# FPGA_Symbol1.net
KiCad netlist of a schematic drawn in Altium Designer
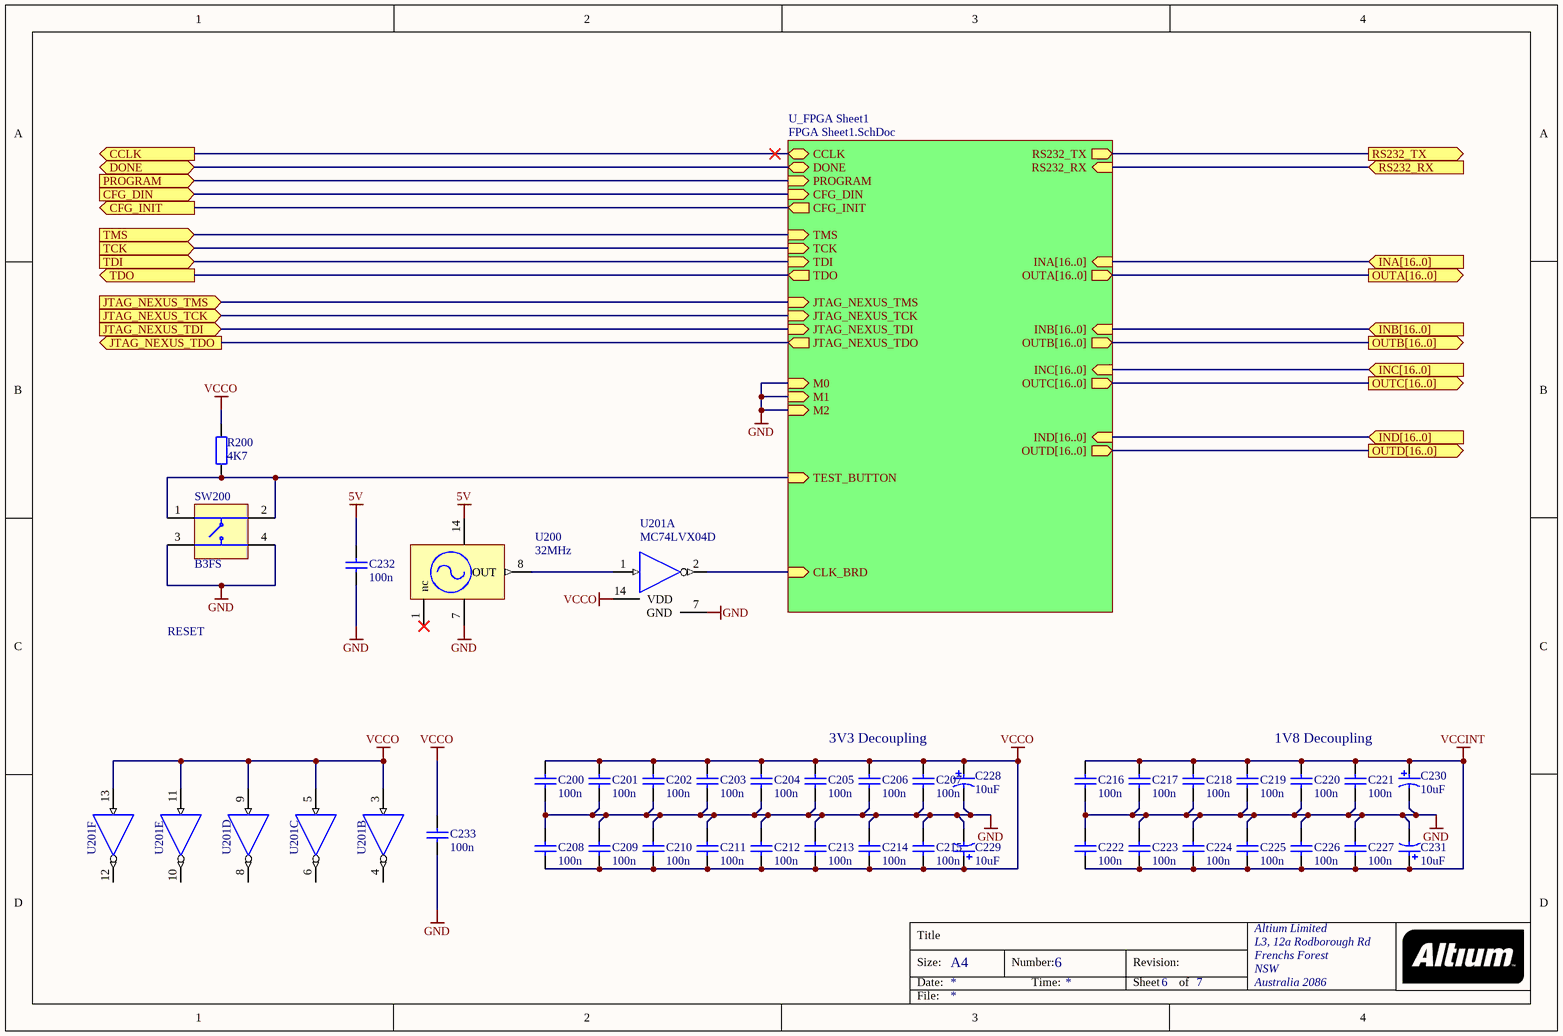
[diagram p0: FPGA Symbol1.SchDoc]

(export (version "E")
  (design (tool "Eeschema 10.0.6"))
  (components
    (comp (ref "C200")
      (value "100n")
      (footprint "BOC1_3:CC2012-0805")
      (description "Capacitor")
      (libsource (lib "BOC1_3") (part "CAP"))
    )
    (comp (ref "C201")
      (value "100n")
      (footprint "BOC1_3:CC2012-0805")
      (description "Capacitor")
      (libsource (lib "BOC1_3") (part "CAP"))
    )
    (comp (ref "C202")
      (value "100n")
      (footprint "BOC1_3:CC2012-0805")
      (description "Capacitor")
      (libsource (lib "BOC1_3") (part "CAP"))
    )
    (comp (ref "C203")
      (value "100n")
      (footprint "BOC1_3:CC2012-0805")
      (description "Capacitor")
      (libsource (lib "BOC1_3") (part "CAP"))
    )
    (comp (ref "C204")
      (value "100n")
      (footprint "BOC1_3:CC2012-0805")
      (description "Capacitor")
      (libsource (lib "BOC1_3") (part "CAP"))
    )
    (comp (ref "C205")
      (value "100n")
      (footprint "BOC1_3:CC2012-0805")
      (description "Capacitor")
      (libsource (lib "BOC1_3") (part "CAP"))
    )
    (comp (ref "C206")
      (value "100n")
      (footprint "BOC1_3:CC2012-0805")
      (description "Capacitor")
      (libsource (lib "BOC1_3") (part "CAP"))
    )
    (comp (ref "C207")
      (value "100n")
      (footprint "BOC1_3:CC2012-0805")
      (description "Capacitor")
      (libsource (lib "BOC1_3") (part "CAP"))
    )
    (comp (ref "C208")
      (value "100n")
      (footprint "BOC1_3:CC2012-0805")
      (description "Capacitor")
      (libsource (lib "BOC1_3") (part "CAP"))
    )
    (comp (ref "C209")
      (value "100n")
      (footprint "BOC1_3:CC2012-0805")
      (description "Capacitor")
      (libsource (lib "BOC1_3") (part "CAP"))
    )
    (comp (ref "C210")
      (value "100n")
      (footprint "BOC1_3:CC2012-0805")
      (description "Capacitor")
      (libsource (lib "BOC1_3") (part "CAP"))
    )
    (comp (ref "C211")
      (value "100n")
      (footprint "BOC1_3:CC2012-0805")
      (description "Capacitor")
      (libsource (lib "BOC1_3") (part "CAP"))
    )
    (comp (ref "C212")
      (value "100n")
      (footprint "BOC1_3:CC2012-0805")
      (description "Capacitor")
      (libsource (lib "BOC1_3") (part "CAP"))
    )
    (comp (ref "C213")
      (value "100n")
      (footprint "BOC1_3:CC2012-0805")
      (description "Capacitor")
      (libsource (lib "BOC1_3") (part "CAP"))
    )
    (comp (ref "C214")
      (value "100n")
      (footprint "BOC1_3:CC2012-0805")
      (description "Capacitor")
      (libsource (lib "BOC1_3") (part "CAP"))
    )
    (comp (ref "C215")
      (value "100n")
      (footprint "BOC1_3:CC2012-0805")
      (description "Capacitor")
      (libsource (lib "BOC1_3") (part "CAP"))
    )
    (comp (ref "C216")
      (value "100n")
      (footprint "BOC1_3:CC2012-0805")
      (description "Capacitor")
      (libsource (lib "BOC1_3") (part "CAP"))
    )
    (comp (ref "C217")
      (value "100n")
      (footprint "BOC1_3:CC2012-0805")
      (description "Capacitor")
      (libsource (lib "BOC1_3") (part "CAP"))
    )
    (comp (ref "C218")
      (value "100n")
      (footprint "BOC1_3:CC2012-0805")
      (description "Capacitor")
      (libsource (lib "BOC1_3") (part "CAP"))
    )
    (comp (ref "C219")
      (value "100n")
      (footprint "BOC1_3:CC2012-0805")
      (description "Capacitor")
      (libsource (lib "BOC1_3") (part "CAP"))
    )
    (comp (ref "C220")
      (value "100n")
      (footprint "BOC1_3:CC2012-0805")
      (description "Capacitor")
      (libsource (lib "BOC1_3") (part "CAP"))
    )
    (comp (ref "C221")
      (value "100n")
      (footprint "BOC1_3:CC2012-0805")
      (description "Capacitor")
      (libsource (lib "BOC1_3") (part "CAP"))
    )
    (comp (ref "C222")
      (value "100n")
      (footprint "BOC1_3:CC2012-0805")
      (description "Capacitor")
      (libsource (lib "BOC1_3") (part "CAP"))
    )
    (comp (ref "C223")
      (value "100n")
      (footprint "BOC1_3:CC2012-0805")
      (description "Capacitor")
      (libsource (lib "BOC1_3") (part "CAP"))
    )
    (comp (ref "C224")
      (value "100n")
      (footprint "BOC1_3:CC2012-0805")
      (description "Capacitor")
      (libsource (lib "BOC1_3") (part "CAP"))
    )
    (comp (ref "C225")
      (value "100n")
      (footprint "BOC1_3:CC2012-0805")
      (description "Capacitor")
      (libsource (lib "BOC1_3") (part "CAP"))
    )
    (comp (ref "C226")
      (value "100n")
      (footprint "BOC1_3:CC2012-0805")
      (description "Capacitor")
      (libsource (lib "BOC1_3") (part "CAP"))
    )
    (comp (ref "C227")
      (value "100n")
      (footprint "BOC1_3:CC2012-0805")
      (description "Capacitor")
      (libsource (lib "BOC1_3") (part "CAP"))
    )
    (comp (ref "C228")
      (value "10uF")
      (footprint "BOC1_3:MCCT-B")
      (description "Polar Capacitor")
      (libsource (lib "BOC1_3") (part "CAP_POLAR"))
    )
    (comp (ref "C229")
      (value "10uF")
      (footprint "BOC1_3:MCCT-B")
      (description "Polar Capacitor")
      (libsource (lib "BOC1_3") (part "CAP_POLAR"))
    )
    (comp (ref "C230")
      (value "10uF")
      (footprint "BOC1_3:MCCT-B")
      (description "Polar Capacitor")
      (libsource (lib "BOC1_3") (part "CAP_POLAR"))
    )
    (comp (ref "C231")
      (value "10uF")
      (footprint "BOC1_3:MCCT-B")
      (description "Polar Capacitor")
      (libsource (lib "BOC1_3") (part "CAP_POLAR"))
    )
    (comp (ref "C232")
      (value "100n")
      (footprint "BOC1_3:CC2012-0805")
      (description "Capacitor")
      (libsource (lib "Miscellaneous Devices") (part "CAP"))
    )
    (comp (ref "C233")
      (value "100n")
      (footprint "BOC1_3:CC2012-0805")
      (description "Capacitor")
      (libsource (lib "Miscellaneous Devices") (part "CAP"))
    )
    (comp (ref "R200")
      (value "4K7")
      (footprint "BOC1_3:CC2012-0805")
      (description "Resistor")
      (fields (field (name "MANUFACTURER") "Generic Components") (field (name "PUBLISHER") "Altium Limited"))
      (libsource (lib "Miscellaneous Devices") (part "Res2"))
    )
    (comp (ref "SW200")
      (value "B3FS")
      (footprint "BOC1_3:B3FS_SWITCH")
      (description "SPNA SMD Keyboard Switch")
      (libsource (lib "switches") (part "B3FS"))
    )
    (comp (ref "U200")
      (value "32MHz")
      (footprint "UIBV1(PCB):XO600CP")
      (description "IC, Oscillator, Canned, CMOS o/p, General Purpose, No Enable/Disable, 32MHz")
      (libsource (lib "PortSwitcher") (part "XO_CAN_DIP14_1M"))
    )
    (comp (ref "U201")
      (value "MC74LVX04D")
      (footprint "751A-03")
      (description "Hex Inverter with 5V-Tolerant Inputs")
      (fields (field (name "MANUFACTURER") "ON Semiconductor") (field (name "PUBLISHER") "Altium Limited"))
      (libsource (lib "PortSwitcher") (part "MC74LVX04D"))
    )
  )
  (nets
    (net (code "140") (name "/CLK_BRD") (class "Default")
      (node (ref "U201") (pin "2") (pinfunction "~{OUT}_2") (pintype "output"))
    )
    (net (code "160") (name "/TEST_BUTTON") (class "Default")
      (node (ref "R200") (pin "1") (pinfunction "1_1") (pintype "passive"))
      (node (ref "SW200") (pin "1") (pinfunction "1_1") (pintype "passive"))
      (node (ref "SW200") (pin "2") (pinfunction "2_2") (pintype "passive"))
    )
    (net (code "162") (name "5V") (class "Default")
      (node (ref "C232") (pin "1") (pinfunction "1_1") (pintype "passive"))
      (node (ref "U200") (pin "14") (pinfunction "VCC_14") (pintype "power_in"))
    )
    (net (code "163") (name "GND") (class "Default")
      (node (ref "C200") (pin "2") (pinfunction "2_2") (pintype "passive"))
      (node (ref "C201") (pin "2") (pinfunction "2_2") (pintype "passive"))
      (node (ref "C202") (pin "2") (pinfunction "2_2") (pintype "passive"))
      (node (ref "C203") (pin "2") (pinfunction "2_2") (pintype "passive"))
      (node (ref "C204") (pin "2") (pinfunction "2_2") (pintype "passive"))
      (node (ref "C205") (pin "2") (pinfunction "2_2") (pintype "passive"))
      (node (ref "C206") (pin "2") (pinfunction "2_2") (pintype "passive"))
      (node (ref "C207") (pin "2") (pinfunction "2_2") (pintype "passive"))
      (node (ref "C208") (pin "1") (pinfunction "1_1") (pintype "passive"))
      (node (ref "C209") (pin "1") (pinfunction "1_1") (pintype "passive"))
      (node (ref "C210") (pin "1") (pinfunction "1_1") (pintype "passive"))
      (node (ref "C211") (pin "1") (pinfunction "1_1") (pintype "passive"))
      (node (ref "C212") (pin "1") (pinfunction "1_1") (pintype "passive"))
      (node (ref "C213") (pin "1") (pinfunction "1_1") (pintype "passive"))
      (node (ref "C214") (pin "1") (pinfunction "1_1") (pintype "passive"))
      (node (ref "C215") (pin "1") (pinfunction "1_1") (pintype "passive"))
      (node (ref "C216") (pin "2") (pinfunction "2_2") (pintype "passive"))
      (node (ref "C217") (pin "2") (pinfunction "2_2") (pintype "passive"))
      (node (ref "C218") (pin "2") (pinfunction "2_2") (pintype "passive"))
      (node (ref "C219") (pin "2") (pinfunction "2_2") (pintype "passive"))
      (node (ref "C220") (pin "2") (pinfunction "2_2") (pintype "passive"))
      (node (ref "C221") (pin "2") (pinfunction "2_2") (pintype "passive"))
      (node (ref "C222") (pin "1") (pinfunction "1_1") (pintype "passive"))
      (node (ref "C223") (pin "1") (pinfunction "1_1") (pintype "passive"))
      (node (ref "C224") (pin "1") (pinfunction "1_1") (pintype "passive"))
      (node (ref "C225") (pin "1") (pinfunction "1_1") (pintype "passive"))
      (node (ref "C226") (pin "1") (pinfunction "1_1") (pintype "passive"))
      (node (ref "C227") (pin "1") (pinfunction "1_1") (pintype "passive"))
      (node (ref "C228") (pin "2") (pinfunction "2_2") (pintype "passive"))
      (node (ref "C229") (pin "2") (pinfunction "2_2") (pintype "passive"))
      (node (ref "C230") (pin "2") (pinfunction "2_2") (pintype "passive"))
      (node (ref "C231") (pin "2") (pinfunction "2_2") (pintype "passive"))
      (node (ref "C232") (pin "2") (pinfunction "2_2") (pintype "passive"))
      (node (ref "C233") (pin "2") (pinfunction "2_2") (pintype "passive"))
      (node (ref "SW200") (pin "3") (pinfunction "3_3") (pintype "passive"))
      (node (ref "SW200") (pin "4") (pinfunction "4_4") (pintype "passive"))
      (node (ref "U200") (pin "7") (pinfunction "GND_7") (pintype "power_in"))
      (node (ref "U201") (pin "7") (pinfunction "GND_7") (pintype "power_in"))
    )
    (net (code "164") (name "Net-(U200-OUT)") (class "Default")
      (node (ref "U200") (pin "8") (pinfunction "OUT_8") (pintype "output"))
      (node (ref "U201") (pin "1") (pinfunction "IN_1") (pintype "input"))
    )
    (net (code "165") (name "VCCINT") (class "Default")
      (node (ref "C216") (pin "1") (pinfunction "1_1") (pintype "passive"))
      (node (ref "C217") (pin "1") (pinfunction "1_1") (pintype "passive"))
      (node (ref "C218") (pin "1") (pinfunction "1_1") (pintype "passive"))
      (node (ref "C219") (pin "1") (pinfunction "1_1") (pintype "passive"))
      (node (ref "C220") (pin "1") (pinfunction "1_1") (pintype "passive"))
      (node (ref "C221") (pin "1") (pinfunction "1_1") (pintype "passive"))
      (node (ref "C222") (pin "2") (pinfunction "2_2") (pintype "passive"))
      (node (ref "C223") (pin "2") (pinfunction "2_2") (pintype "passive"))
      (node (ref "C224") (pin "2") (pinfunction "2_2") (pintype "passive"))
      (node (ref "C225") (pin "2") (pinfunction "2_2") (pintype "passive"))
      (node (ref "C226") (pin "2") (pinfunction "2_2") (pintype "passive"))
      (node (ref "C227") (pin "2") (pinfunction "2_2") (pintype "passive"))
      (node (ref "C230") (pin "1") (pinfunction "1_1") (pintype "passive"))
      (node (ref "C231") (pin "1") (pinfunction "1_1") (pintype "passive"))
    )
    (net (code "166") (name "VCCO") (class "Default")
      (node (ref "C200") (pin "1") (pinfunction "1_1") (pintype "passive"))
      (node (ref "C201") (pin "1") (pinfunction "1_1") (pintype "passive"))
      (node (ref "C202") (pin "1") (pinfunction "1_1") (pintype "passive"))
      (node (ref "C203") (pin "1") (pinfunction "1_1") (pintype "passive"))
      (node (ref "C204") (pin "1") (pinfunction "1_1") (pintype "passive"))
      (node (ref "C205") (pin "1") (pinfunction "1_1") (pintype "passive"))
      (node (ref "C206") (pin "1") (pinfunction "1_1") (pintype "passive"))
      (node (ref "C207") (pin "1") (pinfunction "1_1") (pintype "passive"))
      (node (ref "C208") (pin "2") (pinfunction "2_2") (pintype "passive"))
      (node (ref "C209") (pin "2") (pinfunction "2_2") (pintype "passive"))
      (node (ref "C210") (pin "2") (pinfunction "2_2") (pintype "passive"))
      (node (ref "C211") (pin "2") (pinfunction "2_2") (pintype "passive"))
      (node (ref "C212") (pin "2") (pinfunction "2_2") (pintype "passive"))
      (node (ref "C213") (pin "2") (pinfunction "2_2") (pintype "passive"))
      (node (ref "C214") (pin "2") (pinfunction "2_2") (pintype "passive"))
      (node (ref "C215") (pin "2") (pinfunction "2_2") (pintype "passive"))
      (node (ref "C228") (pin "1") (pinfunction "1_1") (pintype "passive"))
      (node (ref "C229") (pin "1") (pinfunction "1_1") (pintype "passive"))
      (node (ref "C233") (pin "1") (pinfunction "1_1") (pintype "passive"))
      (node (ref "R200") (pin "2") (pinfunction "2_2") (pintype "passive"))
      (node (ref "U201") (pin "11") (pinfunction "IN_11") (pintype "input"))
      (node (ref "U201") (pin "13") (pinfunction "IN_13") (pintype "input"))
      (node (ref "U201") (pin "14") (pinfunction "VDD_14") (pintype "power_in"))
      (node (ref "U201") (pin "3") (pinfunction "IN_3") (pintype "input"))
      (node (ref "U201") (pin "5") (pinfunction "IN_5") (pintype "input"))
      (node (ref "U201") (pin "9") (pinfunction "IN_9") (pintype "input"))
    )
    (net (code "167") (name "unconnected-(U200-nc-Pad1)") (class "Default")
      (node (ref "U200") (pin "1") (pinfunction "nc_1") (pintype "passive+no_connect"))
    )
    (net (code "168") (name "unconnected-(U201B-~{OUT}-Pad4)") (class "Default")
      (node (ref "U201") (pin "4") (pinfunction "~{OUT}_4") (pintype "output"))
    )
    (net (code "169") (name "unconnected-(U201C-~{OUT}-Pad6)") (class "Default")
      (node (ref "U201") (pin "6") (pinfunction "~{OUT}_6") (pintype "output"))
    )
    (net (code "170") (name "unconnected-(U201D-~{OUT}-Pad8)") (class "Default")
      (node (ref "U201") (pin "8") (pinfunction "~{OUT}_8") (pintype "output"))
    )
    (net (code "171") (name "unconnected-(U201E-~{OUT}-Pad10)") (class "Default")
      (node (ref "U201") (pin "10") (pinfunction "~{OUT}_10") (pintype "output"))
    )
    (net (code "172") (name "unconnected-(U201F-~{OUT}-Pad12)") (class "Default")
      (node (ref "U201") (pin "12") (pinfunction "~{OUT}_12") (pintype "output"))
    )
  )
)
